# UARTBreakout-2_0.net
KiCad netlist of a schematic drawn in EAGLE
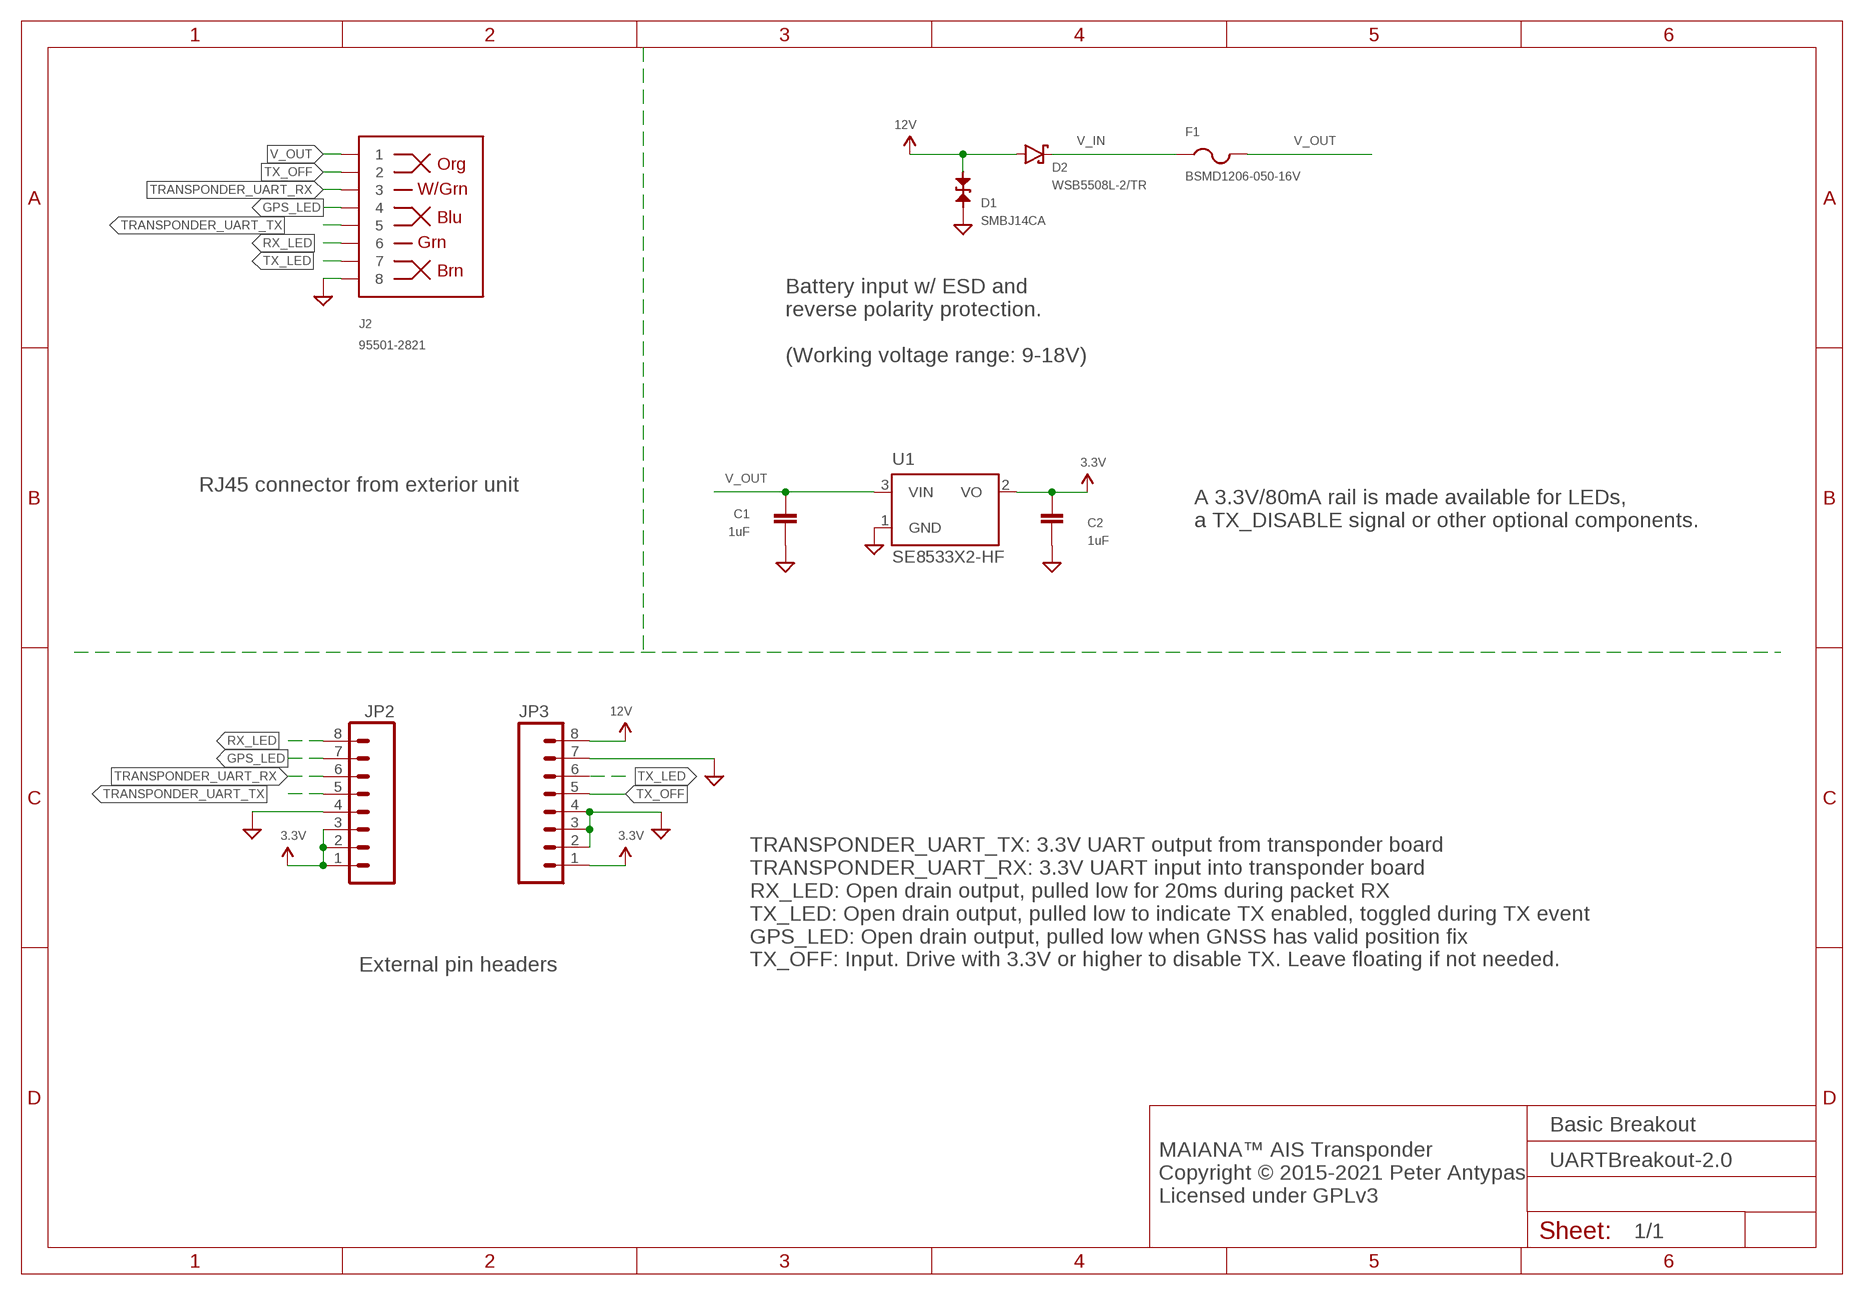
[diagram p0: schematic, sheet 1]

(export (version "E")
  (design (tool "Eeschema 10.0.6"))
  (components
    (comp (ref "C1")
      (value "1uF")
      (footprint "eagle-import:0603")
      (fields (field (name "PARTNO") "CC0603KRX5R8BB105"))
      (libsource (lib "eagle-import") (part "CAPACITOR0603"))
    )
    (comp (ref "C2")
      (value "1uF")
      (footprint "eagle-import:0603")
      (fields (field (name "PARTNO") "CC0603KRX5R8BB105"))
      (libsource (lib "eagle-import") (part "CAPACITOR0603"))
    )
    (comp (ref "D1")
      (value "SMBJ14CA")
      (footprint "eagle-import:SMB-BIDIR")
      (fields (field (name "PARTNO") "SMBJ14CA"))
      (libsource (lib "eagle-import") (part "DIODE-TVS-BIDIRSMB"))
    )
    (comp (ref "D2")
      (value "WSB5508L-2/TR")
      (footprint "eagle-import:SOD123")
      (fields (field (name "PARTNO") "WSB5508L-2/TR"))
      (libsource (lib "eagle-import") (part "DIODE-SCHOTTKYSOD123"))
    )
    (comp (ref "F1")
      (value "BSMD1206-050-16V")
      (footprint "eagle-import:R1206")
      (libsource (lib "eagle-import") (part "PTCFUSE-1206"))
    )
    (comp (ref "J2")
      (value "95501-2821")
      (footprint "eagle-import:RJ45-8")
      (libsource (lib "eagle-import") (part "RJ45-8PTH"))
    )
    (comp (ref "JP2")
      (value "M08SILK_FEMALE_PTH")
      (footprint "eagle-import:1X08")
      (libsource (lib "eagle-import") (part "M08SILK_FEMALE_PTH"))
    )
    (comp (ref "JP3")
      (value "M08SILK_FEMALE_PTH")
      (footprint "eagle-import:1X08")
      (libsource (lib "eagle-import") (part "M08SILK_FEMALE_PTH"))
    )
    (comp (ref "U1")
      (value "SE8533X2-HF")
      (footprint "eagle-import:SOT23")
      (libsource (lib "eagle-import") (part "MCP1799T"))
    )
  )
  (nets
    (net (code "1") (name "/V_IN") (class "Default")
      (node (ref "D2") (pin "C") (pinfunction "C_C") (pintype "passive"))
      (node (ref "F1") (pin "1") (pinfunction "1_1") (pintype "passive"))
    )
    (net (code "2") (name "3.3V") (class "Default")
      (node (ref "C2") (pin "P$1") (pinfunction "1_P$1") (pintype "passive"))
      (node (ref "JP2") (pin "1") (pinfunction "1_1") (pintype "passive"))
      (node (ref "JP2") (pin "2") (pinfunction "2_2") (pintype "passive"))
      (node (ref "JP2") (pin "3") (pinfunction "3_3") (pintype "passive"))
      (node (ref "JP3") (pin "1") (pinfunction "1_1") (pintype "passive"))
      (node (ref "U1") (pin "2") (pinfunction "VO_2") (pintype "output"))
    )
    (net (code "3") (name "12V") (class "Default")
      (node (ref "D1") (pin "A") (pinfunction "P$1_A") (pintype "bidirectional"))
      (node (ref "D2") (pin "A") (pinfunction "A_A") (pintype "passive"))
      (node (ref "JP3") (pin "8") (pinfunction "8_8") (pintype "passive"))
    )
    (net (code "4") (name "GND") (class "Default")
      (node (ref "C1") (pin "P$2") (pinfunction "2_P$2") (pintype "passive"))
      (node (ref "C2") (pin "P$2") (pinfunction "2_P$2") (pintype "passive"))
      (node (ref "D1") (pin "C") (pinfunction "P$2_C") (pintype "bidirectional"))
      (node (ref "J2") (pin "8") (pinfunction "8_8") (pintype "bidirectional"))
      (node (ref "JP2") (pin "4") (pinfunction "4_4") (pintype "passive"))
      (node (ref "JP3") (pin "2") (pinfunction "2_2") (pintype "passive"))
      (node (ref "JP3") (pin "3") (pinfunction "3_3") (pintype "passive"))
      (node (ref "JP3") (pin "4") (pinfunction "4_4") (pintype "passive"))
      (node (ref "JP3") (pin "7") (pinfunction "7_7") (pintype "passive"))
      (node (ref "U1") (pin "1") (pinfunction "GND_1") (pintype "passive"))
    )
    (net (code "5") (name "GPS_LED") (class "Default")
      (node (ref "J2") (pin "4") (pinfunction "4_4") (pintype "bidirectional"))
      (node (ref "JP2") (pin "7") (pinfunction "7_7") (pintype "passive"))
    )
    (net (code "6") (name "RX_LED") (class "Default")
      (node (ref "J2") (pin "6") (pinfunction "6_6") (pintype "bidirectional"))
      (node (ref "JP2") (pin "8") (pinfunction "8_8") (pintype "passive"))
    )
    (net (code "7") (name "TRANSPONDER_UART_RX") (class "Default")
      (node (ref "J2") (pin "3") (pinfunction "3_3") (pintype "bidirectional"))
      (node (ref "JP2") (pin "6") (pinfunction "6_6") (pintype "passive"))
    )
    (net (code "8") (name "TRANSPONDER_UART_TX") (class "Default")
      (node (ref "J2") (pin "5") (pinfunction "5_5") (pintype "bidirectional"))
      (node (ref "JP2") (pin "5") (pinfunction "5_5") (pintype "passive"))
    )
    (net (code "9") (name "TX_LED") (class "Default")
      (node (ref "J2") (pin "7") (pinfunction "7_7") (pintype "bidirectional"))
      (node (ref "JP3") (pin "6") (pinfunction "6_6") (pintype "passive"))
    )
    (net (code "10") (name "TX_OFF") (class "Default")
      (node (ref "J2") (pin "2") (pinfunction "2_2") (pintype "bidirectional"))
      (node (ref "JP3") (pin "5") (pinfunction "5_5") (pintype "passive"))
    )
    (net (code "11") (name "V_OUT") (class "Default")
      (node (ref "C1") (pin "P$1") (pinfunction "1_P$1") (pintype "passive"))
      (node (ref "F1") (pin "2") (pinfunction "2_2") (pintype "passive"))
      (node (ref "J2") (pin "1") (pinfunction "1_1") (pintype "bidirectional"))
      (node (ref "U1") (pin "3") (pinfunction "VIN_3") (pintype "input"))
    )
  )
)
